# Sequencer1.net
KiCad netlist of a schematic drawn in EAGLE
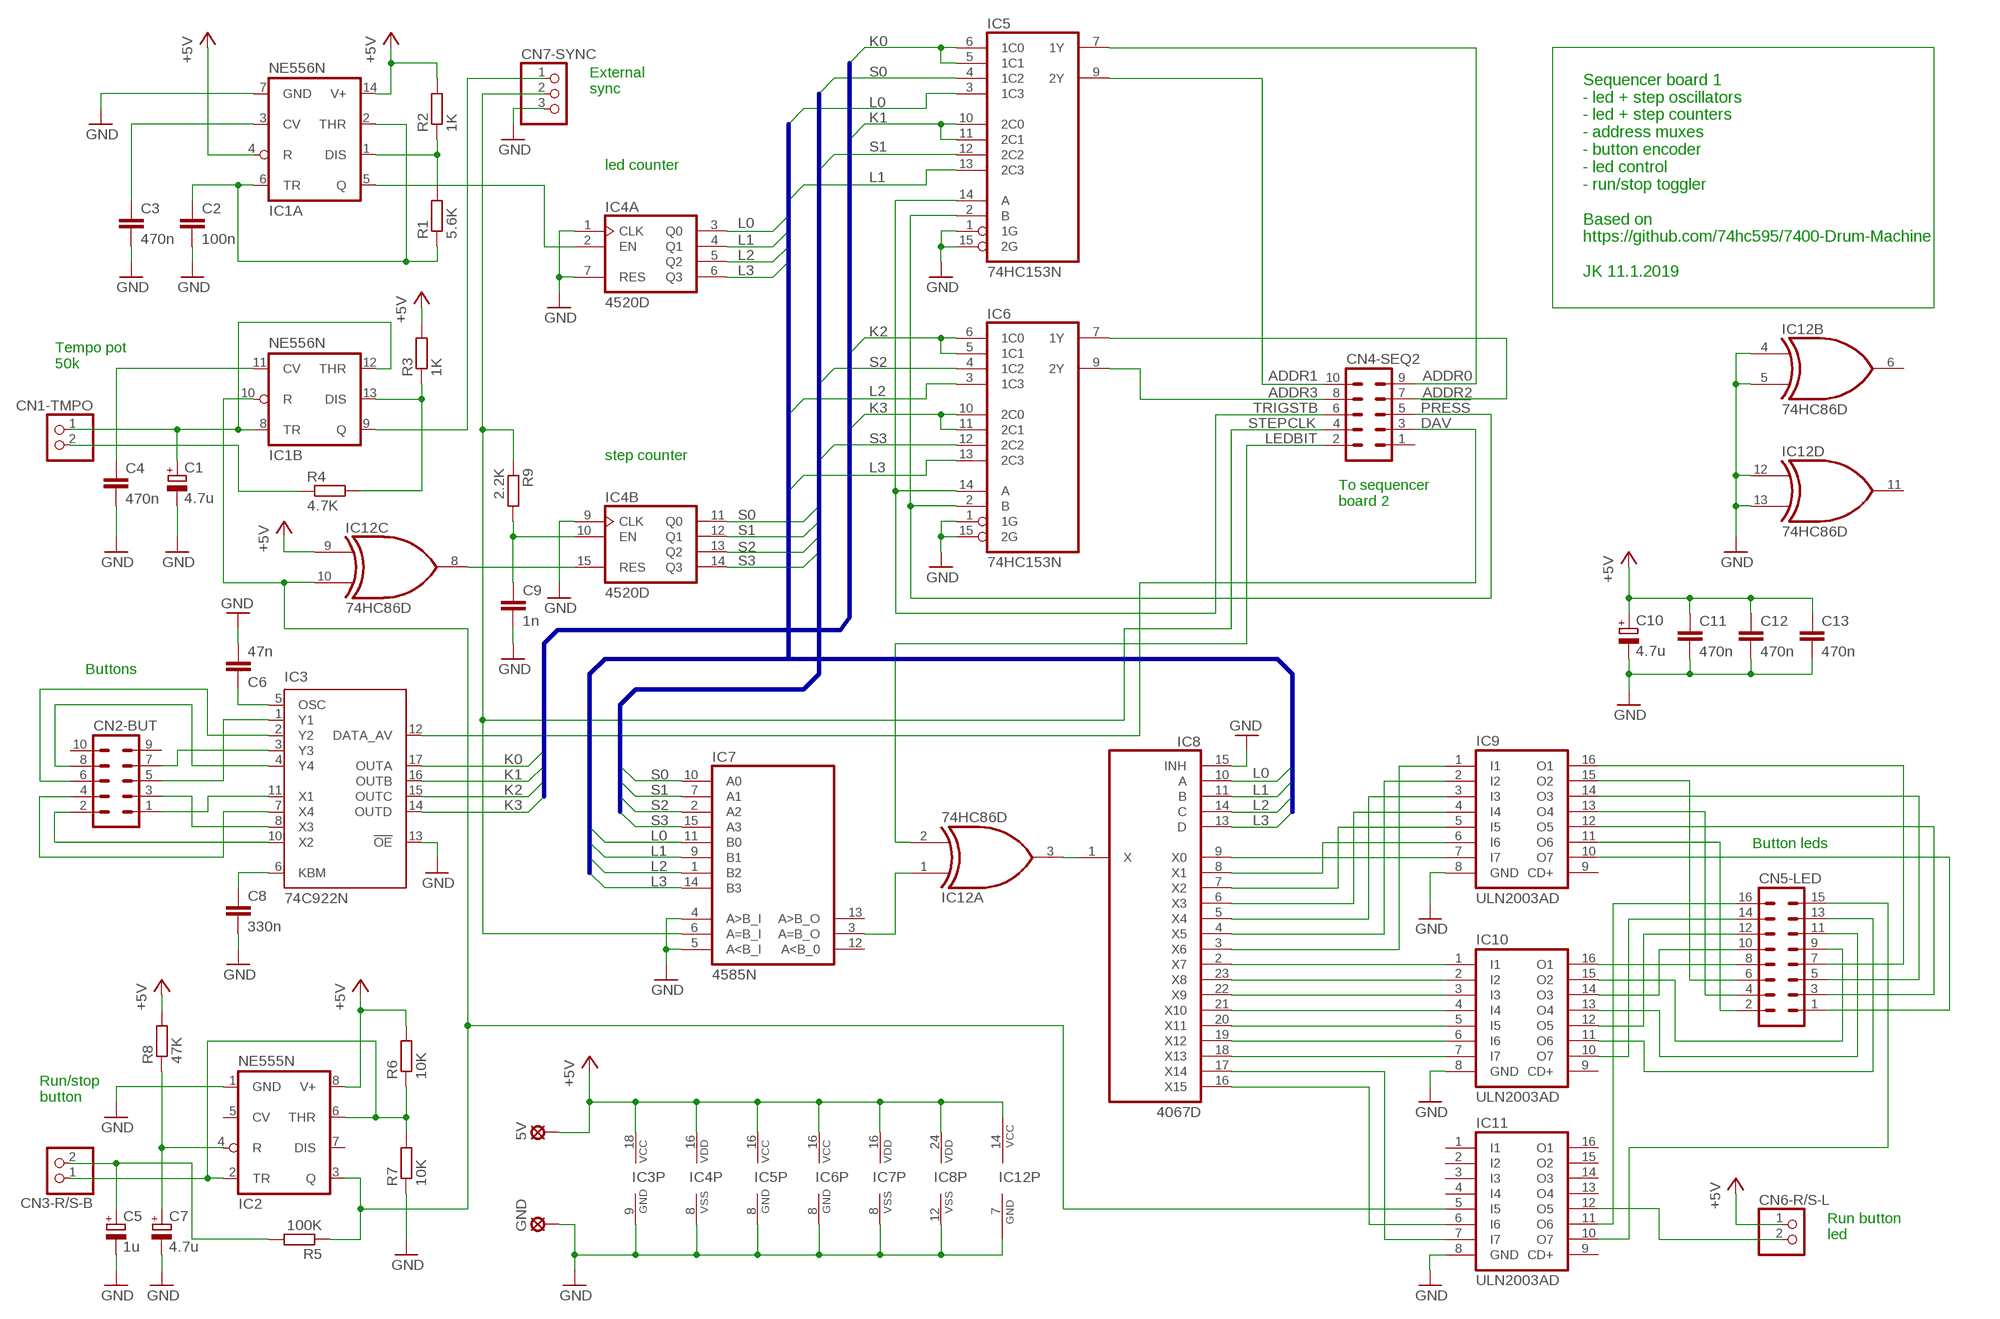
[diagram p0: schematic, sheet 1]

(export (version "E")
  (design (tool "Eeschema 10.0.6"))
  (components
    (comp (ref "5V")
      (value "LSP10")
      (footprint "eagle-import:LSP10")
      (libsource (lib "eagle-import") (part "LSP10"))
    )
    (comp (ref "C1")
      (value "4.7u")
      (footprint "eagle-import:SMC_A")
      (libsource (lib "eagle-import") (part "CPOL-EUSMCA"))
    )
    (comp (ref "C2")
      (value "100n")
      (footprint "eagle-import:C0805")
      (libsource (lib "eagle-import") (part "C-EUC0805"))
    )
    (comp (ref "C3")
      (value "470n")
      (footprint "eagle-import:C0603")
      (libsource (lib "eagle-import") (part "C-EUC0603"))
    )
    (comp (ref "C4")
      (value "470n")
      (footprint "eagle-import:C0603")
      (libsource (lib "eagle-import") (part "C-EUC0603"))
    )
    (comp (ref "C5")
      (value "1u")
      (footprint "eagle-import:SMC_A")
      (libsource (lib "eagle-import") (part "CPOL-EUSMCA"))
    )
    (comp (ref "C6")
      (value "47n")
      (footprint "eagle-import:C0805")
      (libsource (lib "eagle-import") (part "C-EUC0805"))
    )
    (comp (ref "C7")
      (value "4.7u")
      (footprint "eagle-import:SMC_A")
      (libsource (lib "eagle-import") (part "CPOL-EUSMCA"))
    )
    (comp (ref "C8")
      (value "330n")
      (footprint "eagle-import:C0805")
      (libsource (lib "eagle-import") (part "C-EUC0805"))
    )
    (comp (ref "C9")
      (value "1n")
      (footprint "eagle-import:C0805")
      (libsource (lib "eagle-import") (part "C-EUC0805"))
    )
    (comp (ref "C10")
      (value "4.7u")
      (footprint "eagle-import:SMC_A")
      (libsource (lib "eagle-import") (part "CPOL-EUSMCA"))
    )
    (comp (ref "C11")
      (value "470n")
      (footprint "eagle-import:C0603")
      (libsource (lib "eagle-import") (part "C-EUC0603"))
    )
    (comp (ref "C12")
      (value "470n")
      (footprint "eagle-import:C0603")
      (libsource (lib "eagle-import") (part "C-EUC0603"))
    )
    (comp (ref "C13")
      (value "470n")
      (footprint "eagle-import:C0603")
      (libsource (lib "eagle-import") (part "C-EUC0603"))
    )
    (comp (ref "CN1-TMPO")
      (value "PINHD-1X2")
      (footprint "eagle-import:1X02")
      (libsource (lib "eagle-import") (part "PINHD-1X2"))
    )
    (comp (ref "CN2-BUT")
      (value "MA05-2")
      (footprint "eagle-import:MA05-2")
      (libsource (lib "eagle-import") (part "MA05-2"))
    )
    (comp (ref "CN3-R/S-B")
      (value "PINHD-1X2")
      (footprint "eagle-import:1X02")
      (libsource (lib "eagle-import") (part "PINHD-1X2"))
    )
    (comp (ref "CN4-SEQ2")
      (value "MA05-2")
      (footprint "eagle-import:MA05-2")
      (libsource (lib "eagle-import") (part "MA05-2"))
    )
    (comp (ref "CN5-LED")
      (value "MA08-2")
      (footprint "eagle-import:MA08-2")
      (libsource (lib "eagle-import") (part "MA08-2"))
    )
    (comp (ref "CN6-R/S-L")
      (value "PINHD-1X2")
      (footprint "eagle-import:1X02")
      (libsource (lib "eagle-import") (part "PINHD-1X2"))
    )
    (comp (ref "CN7-SYNC")
      (value "PINHD-1X3")
      (footprint "eagle-import:1X03")
      (libsource (lib "eagle-import") (part "PINHD-1X3"))
    )
    (comp (ref "GND")
      (value "LSP10")
      (footprint "eagle-import:LSP10")
      (libsource (lib "eagle-import") (part "LSP10"))
    )
    (comp (ref "IC1")
      (value "NE556N")
      (footprint "eagle-import:DIL14")
      (libsource (lib "eagle-import") (part "556NNE"))
    )
    (comp (ref "IC2")
      (value "NE555N")
      (footprint "eagle-import:DIL08")
      (libsource (lib "eagle-import") (part "555NNE"))
    )
    (comp (ref "IC3")
      (value "74C922N")
      (footprint "eagle-import:DIL18")
      (libsource (lib "eagle-import") (part "74C922N"))
    )
    (comp (ref "IC4")
      (value "4520D")
      (footprint "eagle-import:SO16")
      (libsource (lib "eagle-import") (part "4520D"))
    )
    (comp (ref "IC5")
      (value "74HC153N")
      (footprint "eagle-import:DIL16")
      (libsource (lib "eagle-import") (part "74153NAC"))
    )
    (comp (ref "IC6")
      (value "74HC153N")
      (footprint "eagle-import:DIL16")
      (libsource (lib "eagle-import") (part "74153NAC"))
    )
    (comp (ref "IC7")
      (value "4585N")
      (footprint "eagle-import:DIL16")
      (libsource (lib "eagle-import") (part "4585N"))
    )
    (comp (ref "IC8")
      (value "4067D")
      (footprint "eagle-import:SO24W")
      (libsource (lib "eagle-import") (part "4067D"))
    )
    (comp (ref "IC9")
      (value "ULN2003AD")
      (footprint "eagle-import:SO16")
      (libsource (lib "eagle-import") (part "ULN2003AD"))
    )
    (comp (ref "IC10")
      (value "ULN2003AD")
      (footprint "eagle-import:SO16")
      (libsource (lib "eagle-import") (part "ULN2003AD"))
    )
    (comp (ref "IC11")
      (value "ULN2003AD")
      (footprint "eagle-import:SO16")
      (libsource (lib "eagle-import") (part "ULN2003AD"))
    )
    (comp (ref "IC12")
      (value "74HC86D")
      (footprint "eagle-import:SO14")
      (libsource (lib "eagle-import") (part "7486DLS"))
    )
    (comp (ref "R1")
      (value "5.6K")
      (footprint "eagle-import:R0805")
      (libsource (lib "eagle-import") (part "R-EU_R0805"))
    )
    (comp (ref "R2")
      (value "1K")
      (footprint "eagle-import:R0805")
      (libsource (lib "eagle-import") (part "R-EU_R0805"))
    )
    (comp (ref "R3")
      (value "1K")
      (footprint "eagle-import:R0805")
      (libsource (lib "eagle-import") (part "R-EU_R0805"))
    )
    (comp (ref "R4")
      (value "4.7K")
      (footprint "eagle-import:R0805")
      (libsource (lib "eagle-import") (part "R-EU_R0805"))
    )
    (comp (ref "R5")
      (value "100K")
      (footprint "eagle-import:R0805")
      (libsource (lib "eagle-import") (part "R-EU_R0805"))
    )
    (comp (ref "R6")
      (value "10K")
      (footprint "eagle-import:R0805")
      (libsource (lib "eagle-import") (part "R-EU_R0805"))
    )
    (comp (ref "R7")
      (value "10K")
      (footprint "eagle-import:R0805")
      (libsource (lib "eagle-import") (part "R-EU_R0805"))
    )
    (comp (ref "R8")
      (value "47K")
      (footprint "eagle-import:R0805")
      (libsource (lib "eagle-import") (part "R-EU_R0805"))
    )
    (comp (ref "R9")
      (value "2.2K")
      (footprint "eagle-import:R0805")
      (libsource (lib "eagle-import") (part "R-EU_R0805"))
    )
  )
  (nets
    (net (code "1") (name "+5V") (class "Default")
      (node (ref "5V") (pin "MP") (pinfunction "MP_MP") (pintype "passive"))
      (node (ref "C10") (pin "+") (pinfunction "+_+") (pintype "passive"))
      (node (ref "C11") (pin "1") (pinfunction "1_1") (pintype "passive"))
      (node (ref "C12") (pin "1") (pinfunction "1_1") (pintype "passive"))
      (node (ref "C13") (pin "1") (pinfunction "1_1") (pintype "passive"))
      (node (ref "CN6-R/S-L") (pin "1") (pinfunction "1_1") (pintype "passive"))
      (node (ref "IC1") (pin "14") (pinfunction "V+_14") (pintype "power_in"))
      (node (ref "IC1") (pin "4") (pinfunction "R_4") (pintype "input"))
      (node (ref "IC12") (pin "14") (pinfunction "VCC_14") (pintype "power_in"))
      (node (ref "IC12") (pin "9") (pinfunction "I0_9") (pintype "input"))
      (node (ref "IC2") (pin "8") (pinfunction "V+_8") (pintype "power_in"))
      (node (ref "IC3") (pin "18") (pinfunction "VCC_18") (pintype "power_in"))
      (node (ref "IC4") (pin "16") (pinfunction "VDD_16") (pintype "power_in"))
      (node (ref "IC5") (pin "16") (pinfunction "VCC_16") (pintype "power_in"))
      (node (ref "IC6") (pin "16") (pinfunction "VCC_16") (pintype "power_in"))
      (node (ref "IC7") (pin "16") (pinfunction "VDD_16") (pintype "power_in"))
      (node (ref "IC8") (pin "24") (pinfunction "VDD_24") (pintype "power_in"))
      (node (ref "R2") (pin "2") (pinfunction "2_2") (pintype "passive"))
      (node (ref "R3") (pin "2") (pinfunction "2_2") (pintype "passive"))
      (node (ref "R6") (pin "2") (pinfunction "2_2") (pintype "passive"))
      (node (ref "R8") (pin "2") (pinfunction "2_2") (pintype "passive"))
    )
    (net (code "2") (name "/ADDR0") (class "Default")
      (node (ref "CN4-SEQ2") (pin "9") (pinfunction "9_9") (pintype "passive"))
      (node (ref "IC5") (pin "7") (pinfunction "1Y_7") (pintype "output"))
    )
    (net (code "3") (name "/ADDR1") (class "Default")
      (node (ref "CN4-SEQ2") (pin "10") (pinfunction "10_10") (pintype "passive"))
      (node (ref "IC5") (pin "9") (pinfunction "2Y_9") (pintype "output"))
    )
    (net (code "4") (name "/ADDR2") (class "Default")
      (node (ref "CN4-SEQ2") (pin "7") (pinfunction "7_7") (pintype "passive"))
      (node (ref "IC6") (pin "7") (pinfunction "1Y_7") (pintype "output"))
    )
    (net (code "5") (name "/ADDR3") (class "Default")
      (node (ref "CN4-SEQ2") (pin "8") (pinfunction "8_8") (pintype "passive"))
      (node (ref "IC6") (pin "9") (pinfunction "2Y_9") (pintype "output"))
    )
    (net (code "6") (name "/DAV") (class "Default")
      (node (ref "CN4-SEQ2") (pin "3") (pinfunction "3_3") (pintype "passive"))
      (node (ref "IC3") (pin "12") (pinfunction "DATA_AV_12") (pintype "output"))
    )
    (net (code "7") (name "/K0") (class "Default")
      (node (ref "IC3") (pin "17") (pinfunction "OUTA_17") (pintype "output"))
      (node (ref "IC5") (pin "5") (pinfunction "1C1_5") (pintype "input"))
      (node (ref "IC5") (pin "6") (pinfunction "1C0_6") (pintype "input"))
    )
    (net (code "8") (name "/K1") (class "Default")
      (node (ref "IC3") (pin "16") (pinfunction "OUTB_16") (pintype "output"))
      (node (ref "IC5") (pin "10") (pinfunction "2C0_10") (pintype "input"))
      (node (ref "IC5") (pin "11") (pinfunction "2C1_11") (pintype "input"))
    )
    (net (code "9") (name "/K2") (class "Default")
      (node (ref "IC3") (pin "15") (pinfunction "OUTC_15") (pintype "output"))
      (node (ref "IC6") (pin "5") (pinfunction "1C1_5") (pintype "input"))
      (node (ref "IC6") (pin "6") (pinfunction "1C0_6") (pintype "input"))
    )
    (net (code "10") (name "/K3") (class "Default")
      (node (ref "IC3") (pin "14") (pinfunction "OUTD_14") (pintype "output"))
      (node (ref "IC6") (pin "10") (pinfunction "2C0_10") (pintype "input"))
      (node (ref "IC6") (pin "11") (pinfunction "2C1_11") (pintype "input"))
    )
    (net (code "11") (name "/L0") (class "Default")
      (node (ref "IC4") (pin "3") (pinfunction "Q0_3") (pintype "output"))
      (node (ref "IC5") (pin "3") (pinfunction "1C3_3") (pintype "input"))
      (node (ref "IC7") (pin "11") (pinfunction "B0_11") (pintype "input"))
      (node (ref "IC8") (pin "10") (pinfunction "A_10") (pintype "input"))
    )
    (net (code "12") (name "/L1") (class "Default")
      (node (ref "IC4") (pin "4") (pinfunction "Q1_4") (pintype "output"))
      (node (ref "IC5") (pin "13") (pinfunction "2C3_13") (pintype "input"))
      (node (ref "IC7") (pin "9") (pinfunction "B1_9") (pintype "input"))
      (node (ref "IC8") (pin "11") (pinfunction "B_11") (pintype "input"))
    )
    (net (code "13") (name "/L2") (class "Default")
      (node (ref "IC4") (pin "5") (pinfunction "Q2_5") (pintype "output"))
      (node (ref "IC6") (pin "3") (pinfunction "1C3_3") (pintype "input"))
      (node (ref "IC7") (pin "1") (pinfunction "B2_1") (pintype "input"))
      (node (ref "IC8") (pin "14") (pinfunction "C_14") (pintype "input"))
    )
    (net (code "14") (name "/L3") (class "Default")
      (node (ref "IC4") (pin "6") (pinfunction "Q3_6") (pintype "output"))
      (node (ref "IC6") (pin "13") (pinfunction "2C3_13") (pintype "input"))
      (node (ref "IC7") (pin "14") (pinfunction "B3_14") (pintype "input"))
      (node (ref "IC8") (pin "13") (pinfunction "D_13") (pintype "input"))
    )
    (net (code "15") (name "/LEDBIT") (class "Default")
      (node (ref "CN4-SEQ2") (pin "2") (pinfunction "2_2") (pintype "passive"))
      (node (ref "IC12") (pin "2") (pinfunction "I1_2") (pintype "input"))
    )
    (net (code "16") (name "/S0") (class "Default")
      (node (ref "IC4") (pin "11") (pinfunction "Q0_11") (pintype "output"))
      (node (ref "IC5") (pin "4") (pinfunction "1C2_4") (pintype "input"))
      (node (ref "IC7") (pin "10") (pinfunction "A0_10") (pintype "input"))
    )
    (net (code "17") (name "/S1") (class "Default")
      (node (ref "IC4") (pin "12") (pinfunction "Q1_12") (pintype "output"))
      (node (ref "IC5") (pin "12") (pinfunction "2C2_12") (pintype "input"))
      (node (ref "IC7") (pin "7") (pinfunction "A1_7") (pintype "input"))
    )
    (net (code "18") (name "/S2") (class "Default")
      (node (ref "IC4") (pin "13") (pinfunction "Q2_13") (pintype "output"))
      (node (ref "IC6") (pin "4") (pinfunction "1C2_4") (pintype "input"))
      (node (ref "IC7") (pin "2") (pinfunction "A2_2") (pintype "input"))
    )
    (net (code "19") (name "/S3") (class "Default")
      (node (ref "IC4") (pin "14") (pinfunction "Q3_14") (pintype "output"))
      (node (ref "IC6") (pin "12") (pinfunction "2C2_12") (pintype "input"))
      (node (ref "IC7") (pin "15") (pinfunction "A3_15") (pintype "input"))
    )
    (net (code "20") (name "/STEPCLK") (class "Default")
      (node (ref "CN4-SEQ2") (pin "4") (pinfunction "4_4") (pintype "passive"))
      (node (ref "CN7-SYNC") (pin "2") (pinfunction "2_2") (pintype "passive"))
      (node (ref "IC7") (pin "6") (pinfunction "A=B_I_6") (pintype "input"))
      (node (ref "R9") (pin "1") (pinfunction "1_1") (pintype "passive"))
    )
    (net (code "21") (name "/TRIGSTB") (class "Default")
      (node (ref "CN4-SEQ2") (pin "6") (pinfunction "6_6") (pintype "passive"))
      (node (ref "IC5") (pin "14") (pinfunction "A_14") (pintype "input"))
      (node (ref "IC6") (pin "14") (pinfunction "A_14") (pintype "input"))
    )
    (net (code "22") (name "/~{PRESS}") (class "Default")
      (node (ref "CN4-SEQ2") (pin "5") (pinfunction "5_5") (pintype "passive"))
      (node (ref "IC5") (pin "2") (pinfunction "B_2") (pintype "input"))
      (node (ref "IC6") (pin "2") (pinfunction "B_2") (pintype "input"))
    )
    (net (code "23") (name "GND") (class "Default")
      (node (ref "C1") (pin "-") (pinfunction "-_-") (pintype "passive"))
      (node (ref "C10") (pin "-") (pinfunction "-_-") (pintype "passive"))
      (node (ref "C11") (pin "2") (pinfunction "2_2") (pintype "passive"))
      (node (ref "C12") (pin "2") (pinfunction "2_2") (pintype "passive"))
      (node (ref "C13") (pin "2") (pinfunction "2_2") (pintype "passive"))
      (node (ref "C2") (pin "2") (pinfunction "2_2") (pintype "passive"))
      (node (ref "C3") (pin "2") (pinfunction "2_2") (pintype "passive"))
      (node (ref "C4") (pin "2") (pinfunction "2_2") (pintype "passive"))
      (node (ref "C5") (pin "-") (pinfunction "-_-") (pintype "passive"))
      (node (ref "C6") (pin "2") (pinfunction "2_2") (pintype "passive"))
      (node (ref "C7") (pin "-") (pinfunction "-_-") (pintype "passive"))
      (node (ref "C8") (pin "2") (pinfunction "2_2") (pintype "passive"))
      (node (ref "C9") (pin "2") (pinfunction "2_2") (pintype "passive"))
      (node (ref "CN7-SYNC") (pin "3") (pinfunction "3_3") (pintype "passive"))
      (node (ref "GND") (pin "MP") (pinfunction "MP_MP") (pintype "passive"))
      (node (ref "IC1") (pin "7") (pinfunction "GND_7") (pintype "power_in"))
      (node (ref "IC10") (pin "8") (pinfunction "GND_8") (pintype "power_in"))
      (node (ref "IC11") (pin "8") (pinfunction "GND_8") (pintype "power_in"))
      (node (ref "IC12") (pin "12") (pinfunction "I0_12") (pintype "input"))
      (node (ref "IC12") (pin "13") (pinfunction "I1_13") (pintype "input"))
      (node (ref "IC12") (pin "4") (pinfunction "I0_4") (pintype "input"))
      (node (ref "IC12") (pin "5") (pinfunction "I1_5") (pintype "input"))
      (node (ref "IC12") (pin "7") (pinfunction "GND_7") (pintype "power_in"))
      (node (ref "IC2") (pin "1") (pinfunction "GND_1") (pintype "power_in"))
      (node (ref "IC3") (pin "13") (pinfunction "~{OE}_13") (pintype "input"))
      (node (ref "IC3") (pin "9") (pinfunction "GND_9") (pintype "power_in"))
      (node (ref "IC4") (pin "1") (pinfunction "CLK_1") (pintype "input"))
      (node (ref "IC4") (pin "7") (pinfunction "RES_7") (pintype "input"))
      (node (ref "IC4") (pin "8") (pinfunction "VSS_8") (pintype "power_in"))
      (node (ref "IC4") (pin "9") (pinfunction "CLK_9") (pintype "input"))
      (node (ref "IC5") (pin "1") (pinfunction "1G_1") (pintype "input"))
      (node (ref "IC5") (pin "15") (pinfunction "2G_15") (pintype "input"))
      (node (ref "IC5") (pin "8") (pinfunction "GND_8") (pintype "power_in"))
      (node (ref "IC6") (pin "1") (pinfunction "1G_1") (pintype "input"))
      (node (ref "IC6") (pin "15") (pinfunction "2G_15") (pintype "input"))
      (node (ref "IC6") (pin "8") (pinfunction "GND_8") (pintype "power_in"))
      (node (ref "IC7") (pin "4") (pinfunction "A>B_I_4") (pintype "input"))
      (node (ref "IC7") (pin "5") (pinfunction "A<B_I_5") (pintype "input"))
      (node (ref "IC7") (pin "8") (pinfunction "VSS_8") (pintype "power_in"))
      (node (ref "IC8") (pin "12") (pinfunction "VSS_12") (pintype "power_in"))
      (node (ref "IC8") (pin "15") (pinfunction "INH_15") (pintype "input"))
      (node (ref "IC9") (pin "8") (pinfunction "GND_8") (pintype "power_in"))
      (node (ref "R7") (pin "1") (pinfunction "1_1") (pintype "passive"))
    )
    (net (code "24") (name "Net-(C5-Pad+)") (class "Default")
      (node (ref "C5") (pin "+") (pinfunction "+_+") (pintype "passive"))
      (node (ref "CN3-R/S-B") (pin "2") (pinfunction "2_2") (pintype "passive"))
      (node (ref "R5") (pin "2") (pinfunction "2_2") (pintype "passive"))
    )
    (net (code "25") (name "Net-(CN1-TMPO-Pad2)") (class "Default")
      (node (ref "CN1-TMPO") (pin "2") (pinfunction "2_2") (pintype "passive"))
      (node (ref "R4") (pin "1") (pinfunction "1_1") (pintype "passive"))
    )
    (net (code "26") (name "Net-(IC1A-CV)") (class "Default")
      (node (ref "C3") (pin "1") (pinfunction "1_1") (pintype "passive"))
      (node (ref "IC1") (pin "3") (pinfunction "CV_3") (pintype "input"))
    )
    (net (code "27") (name "Net-(IC1A-DIS)") (class "Default")
      (node (ref "IC1") (pin "1") (pinfunction "DIS_1") (pintype "input"))
      (node (ref "R1") (pin "2") (pinfunction "2_2") (pintype "passive"))
      (node (ref "R2") (pin "1") (pinfunction "1_1") (pintype "passive"))
    )
    (net (code "28") (name "Net-(IC1A-Q)") (class "Default")
      (node (ref "IC1") (pin "5") (pinfunction "Q_5") (pintype "output"))
      (node (ref "IC4") (pin "2") (pinfunction "EN_2") (pintype "input"))
    )
    (net (code "29") (name "Net-(IC1A-THR)") (class "Default")
      (node (ref "C2") (pin "1") (pinfunction "1_1") (pintype "passive"))
      (node (ref "IC1") (pin "2") (pinfunction "THR_2") (pintype "input"))
      (node (ref "IC1") (pin "6") (pinfunction "TR_6") (pintype "input"))
      (node (ref "R1") (pin "1") (pinfunction "1_1") (pintype "passive"))
    )
    (net (code "30") (name "Net-(IC1B-CV)") (class "Default")
      (node (ref "C4") (pin "1") (pinfunction "1_1") (pintype "passive"))
      (node (ref "IC1") (pin "11") (pinfunction "CV_11") (pintype "input"))
    )
    (net (code "31") (name "Net-(IC1B-DIS)") (class "Default")
      (node (ref "IC1") (pin "13") (pinfunction "DIS_13") (pintype "input"))
      (node (ref "R3") (pin "1") (pinfunction "1_1") (pintype "passive"))
      (node (ref "R4") (pin "2") (pinfunction "2_2") (pintype "passive"))
    )
    (net (code "32") (name "Net-(IC1B-Q)") (class "Default")
      (node (ref "CN7-SYNC") (pin "1") (pinfunction "1_1") (pintype "passive"))
      (node (ref "IC1") (pin "9") (pinfunction "Q_9") (pintype "output"))
    )
    (net (code "33") (name "Net-(IC1B-THR)") (class "Default")
      (node (ref "C1") (pin "+") (pinfunction "+_+") (pintype "passive"))
      (node (ref "CN1-TMPO") (pin "1") (pinfunction "1_1") (pintype "passive"))
      (node (ref "IC1") (pin "12") (pinfunction "THR_12") (pintype "input"))
      (node (ref "IC1") (pin "8") (pinfunction "TR_8") (pintype "input"))
    )
    (net (code "34") (name "Net-(IC2-R)") (class "Default")
      (node (ref "C7") (pin "+") (pinfunction "+_+") (pintype "passive"))
      (node (ref "IC2") (pin "4") (pinfunction "R_4") (pintype "input"))
      (node (ref "R8") (pin "1") (pinfunction "1_1") (pintype "passive"))
    )
    (net (code "35") (name "Net-(IC2-THR)") (class "Default")
      (node (ref "CN3-R/S-B") (pin "1") (pinfunction "1_1") (pintype "passive"))
      (node (ref "IC2") (pin "2") (pinfunction "TR_2") (pintype "input"))
      (node (ref "IC2") (pin "6") (pinfunction "THR_6") (pintype "input"))
      (node (ref "R6") (pin "1") (pinfunction "1_1") (pintype "passive"))
      (node (ref "R7") (pin "2") (pinfunction "2_2") (pintype "passive"))
    )
    (net (code "36") (name "Net-(IC3A-KBM)") (class "Default")
      (node (ref "C8") (pin "1") (pinfunction "1_1") (pintype "passive"))
      (node (ref "IC3") (pin "6") (pinfunction "KBM_6") (pintype "input"))
    )
    (net (code "37") (name "Net-(IC3A-OSC)") (class "Default")
      (node (ref "C6") (pin "1") (pinfunction "1_1") (pintype "passive"))
      (node (ref "IC3") (pin "5") (pinfunction "OSC_5") (pintype "input"))
    )
    (net (code "38") (name "Net-(IC3A-X1)") (class "Default")
      (node (ref "CN2-BUT") (pin "1") (pinfunction "1_1") (pintype "passive"))
      (node (ref "IC3") (pin "11") (pinfunction "X1_11") (pintype "input"))
    )
    (net (code "39") (name "Net-(IC3A-X2)") (class "Default")
      (node (ref "CN2-BUT") (pin "2") (pinfunction "2_2") (pintype "passive"))
      (node (ref "IC3") (pin "10") (pinfunction "X2_10") (pintype "input"))
    )
    (net (code "40") (name "Net-(IC3A-X3)") (class "Default")
      (node (ref "CN2-BUT") (pin "3") (pinfunction "3_3") (pintype "passive"))
      (node (ref "IC3") (pin "8") (pinfunction "X3_8") (pintype "input"))
    )
    (net (code "41") (name "Net-(IC3A-X4)") (class "Default")
      (node (ref "CN2-BUT") (pin "4") (pinfunction "4_4") (pintype "passive"))
      (node (ref "IC3") (pin "7") (pinfunction "X4_7") (pintype "input"))
    )
    (net (code "42") (name "Net-(IC3A-Y1)") (class "Default")
      (node (ref "CN2-BUT") (pin "5") (pinfunction "5_5") (pintype "passive"))
      (node (ref "IC3") (pin "1") (pinfunction "Y1_1") (pintype "input"))
    )
    (net (code "43") (name "Net-(IC3A-Y2)") (class "Default")
      (node (ref "CN2-BUT") (pin "6") (pinfunction "6_6") (pintype "passive"))
      (node (ref "IC3") (pin "2") (pinfunction "Y2_2") (pintype "input"))
    )
    (net (code "44") (name "Net-(IC3A-Y3)") (class "Default")
      (node (ref "CN2-BUT") (pin "7") (pinfunction "7_7") (pintype "passive"))
      (node (ref "IC3") (pin "3") (pinfunction "Y3_3") (pintype "input"))
    )
    (net (code "45") (name "Net-(IC3A-Y4)") (class "Default")
      (node (ref "CN2-BUT") (pin "8") (pinfunction "8_8") (pintype "passive"))
      (node (ref "IC3") (pin "4") (pinfunction "Y4_4") (pintype "input"))
    )
    (net (code "46") (name "Net-(IC4B-EN)") (class "Default")
      (node (ref "C9") (pin "1") (pinfunction "1_1") (pintype "passive"))
      (node (ref "IC4") (pin "10") (pinfunction "EN_10") (pintype "input"))
      (node (ref "R9") (pin "2") (pinfunction "2_2") (pintype "passive"))
    )
    (net (code "47") (name "Net-(IC8A-X0)") (class "Default")
      (node (ref "IC8") (pin "9") (pinfunction "X0_9") (pintype "input"))
      (node (ref "IC9") (pin "7") (pinfunction "I7_7") (pintype "input"))
    )
    (net (code "48") (name "Net-(IC8A-X1)") (class "Default")
      (node (ref "IC8") (pin "8") (pinfunction "X1_8") (pintype "input"))
      (node (ref "IC9") (pin "6") (pinfunction "I6_6") (pintype "input"))
    )
    (net (code "49") (name "Net-(IC8A-X2)") (class "Default")
      (node (ref "IC8") (pin "7") (pinfunction "X2_7") (pintype "input"))
      (node (ref "IC9") (pin "5") (pinfunction "I5_5") (pintype "input"))
    )
    (net (code "50") (name "Net-(IC8A-X3)") (class "Default")
      (node (ref "IC8") (pin "6") (pinfunction "X3_6") (pintype "input"))
      (node (ref "IC9") (pin "4") (pinfunction "I4_4") (pintype "input"))
    )
    (net (code "51") (name "Net-(IC8A-X4)") (class "Default")
      (node (ref "IC8") (pin "5") (pinfunction "X4_5") (pintype "input"))
      (node (ref "IC9") (pin "3") (pinfunction "I3_3") (pintype "input"))
    )
    (net (code "52") (name "Net-(IC8A-X5)") (class "Default")
      (node (ref "IC8") (pin "4") (pinfunction "X5_4") (pintype "input"))
      (node (ref "IC9") (pin "2") (pinfunction "I2_2") (pintype "input"))
    )
    (net (code "53") (name "Net-(IC8A-X6)") (class "Default")
      (node (ref "IC8") (pin "3") (pinfunction "X6_3") (pintype "input"))
      (node (ref "IC9") (pin "1") (pinfunction "I1_1") (pintype "input"))
    )
    (net (code "54") (name "Net-(IC9-O1)") (class "Default")
      (node (ref "CN5-LED") (pin "7") (pinfunction "7_7") (pintype "passive"))
      (node (ref "IC9") (pin "16") (pinfunction "O1_16") (pintype "open_collector"))
    )
    (net (code "55") (name "Net-(IC9-O2)") (class "Default")
      (node (ref "CN5-LED") (pin "6") (pinfunction "6_6") (pintype "passive"))
      (node (ref "IC9") (pin "15") (pinfunction "O2_15") (pintype "open_collector"))
    )
    (net (code "56") (name "Net-(IC9-O3)") (class "Default")
      (node (ref "CN5-LED") (pin "5") (pinfunction "5_5") (pintype "passive"))
      (node (ref "IC9") (pin "14") (pinfunction "O3_14") (pintype "open_collector"))
    )
    (net (code "57") (name "Net-(IC9-O4)") (class "Default")
      (node (ref "CN5-LED") (pin "4") (pinfunction "4_4") (pintype "passive"))
      (node (ref "IC9") (pin "13") (pinfunction "O4_13") (pintype "open_collector"))
    )
    (net (code "58") (name "Net-(IC9-O5)") (class "Default")
      (node (ref "CN5-LED") (pin "3") (pinfunction "3_3") (pintype "passive"))
      (node (ref "IC9") (pin "12") (pinfunction "O5_12") (pintype "open_collector"))
    )
    (net (code "59") (name "Net-(IC9-O6)") (class "Default")
      (node (ref "CN5-LED") (pin "2") (pinfunction "2_2") (pintype "passive"))
      (node (ref "IC9") (pin "11") (pinfunction "O6_11") (pintype "open_collector"))
    )
    (net (code "60") (name "Net-(IC9-O7)") (class "Default")
      (node (ref "CN5-LED") (pin "1") (pinfunction "1_1") (pintype "passive"))
      (node (ref "IC9") (pin "10") (pinfunction "O7_10") (pintype "open_collector"))
    )
    (net (code "61") (name "Net-(IC10-I1)") (class "Default")
      (node (ref "IC10") (pin "1") (pinfunction "I1_1") (pintype "input"))
      (node (ref "IC8") (pin "2") (pinfunction "X7_2") (pintype "input"))
    )
    (net (code "62") (name "Net-(IC10-I2)") (class "Default")
      (node (ref "IC10") (pin "2") (pinfunction "I2_2") (pintype "input"))
      (node (ref "IC8") (pin "23") (pinfunction "X8_23") (pintype "input"))
    )
    (net (code "63") (name "Net-(IC10-I3)") (class "Default")
      (node (ref "IC10") (pin "3") (pinfunction "I3_3") (pintype "input"))
      (node (ref "IC8") (pin "22") (pinfunction "X9_22") (pintype "input"))
    )
    (net (code "64") (name "Net-(IC10-I4)") (class "Default")
      (node (ref "IC10") (pin "4") (pinfunction "I4_4") (pintype "input"))
      (node (ref "IC8") (pin "21") (pinfunction "X10_21") (pintype "input"))
    )
    (net (code "65") (name "Net-(IC10-I5)") (class "Default")
      (node (ref "IC10") (pin "5") (pinfunction "I5_5") (pintype "input"))
      (node (ref "IC8") (pin "20") (pinfunction "X11_20") (pintype "input"))
    )
    (net (code "66") (name "Net-(IC10-I6)") (class "Default")
      (node (ref "IC10") (pin "6") (pinfunction "I6_6") (pintype "input"))
      (node (ref "IC8") (pin "19") (pinfunction "X12_19") (pintype "input"))
    )
    (net (code "67") (name "Net-(IC10-I7)") (class "Default")
      (node (ref "IC10") (pin "7") (pinfunction "I7_7") (pintype "input"))
      (node (ref "IC8") (pin "18") (pinfunction "X13_18") (pintype "input"))
    )
    (net (code "68") (name "Net-(IC10-O1)") (class "Default")
      (node (ref "CN5-LED") (pin "8") (pinfunction "8_8") (pintype "passive"))
      (node (ref "IC10") (pin "16") (pinfunction "O1_16") (pintype "open_collector"))
    )
    (net (code "69") (name "Net-(IC10-O2)") (class "Default")
      (node (ref "CN5-LED") (pin "9") (pinfunction "9_9") (pintype "passive"))
      (node (ref "IC10") (pin "15") (pinfunction "O2_15") (pintype "open_collector"))
    )
    (net (code "70") (name "Net-(IC10-O3)") (class "Default")
      (node (ref "CN5-LED") (pin "10") (pinfunction "10_10") (pintype "passive"))
      (node (ref "IC10") (pin "14") (pinfunction "O3_14") (pintype "open_collector"))
    )
    (net (code "71") (name "Net-(IC10-O4)") (class "Default")
      (node (ref "CN5-LED") (pin "11") (pinfunction "11_11") (pintype "passive"))
      (node (ref "IC10") (pin "13") (pinfunction "O4_13") (pintype "open_collector"))
    )
    (net (code "72") (name "Net-(IC10-O5)") (class "Default")
      (node (ref "CN5-LED") (pin "12") (pinfunction "12_12") (pintype "passive"))
      (node (ref "IC10") (pin "12") (pinfunction "O5_12") (pintype "open_collector"))
    )
    (net (code "73") (name "Net-(IC10-O6)") (class "Default")
      (node (ref "CN5-LED") (pin "13") (pinfunction "13_13") (pintype "passive"))
      (node (ref "IC10") (pin "11") (pinfunction "O6_11") (pintype "open_collector"))
    )
    (net (code "74") (name "Net-(IC10-O7)") (class "Default")
      (node (ref "CN5-LED") (pin "14") (pinfunction "14_14") (pintype "passive"))
      (node (ref "IC10") (pin "10") (pinfunction "O7_10") (pintype "open_collector"))
    )
    (net (code "75") (name "Net-(IC11-I5)") (class "Default")
      (node (ref "IC1") (pin "10") (pinfunction "R_10") (pintype "input"))
      (node (ref "IC11") (pin "5") (pinfunction "I5_5") (pintype "input"))
      (node (ref "IC12") (pin "10") (pinfunction "I1_10") (pintype "input"))
      (node (ref "IC2") (pin "3") (pinfunction "Q_3") (pintype "output"))
      (node (ref "R5") (pin "1") (pinfunction "1_1") (pintype "passive"))
    )
    (net (code "76") (name "Net-(IC11-I6)") (class "Default")
      (node (ref "IC11") (pin "6") (pinfunction "I6_6") (pintype "input"))
      (node (ref "IC8") (pin "16") (pinfunction "X15_16") (pintype "input"))
    )
    (net (code "77") (name "Net-(IC11-I7)") (class "Default")
      (node (ref "IC11") (pin "7") (pinfunction "I7_7") (pintype "input"))
      (node (ref "IC8") (pin "17") (pinfunction "X14_17") (pintype "input"))
    )
    (net (code "78") (name "Net-(IC11-O5)") (class "Default")
      (node (ref "CN6-R/S-L") (pin "2") (pinfunction "2_2") (pintype "passive"))
      (node (ref "IC11") (pin "12") (pinfunction "O5_12") (pintype "open_collector"))
    )
    (net (code "79") (name "Net-(IC11-O6)") (class "Default")
      (node (ref "CN5-LED") (pin "16") (pinfunction "16_16") (pintype "passive"))
      (node (ref "IC11") (pin "11") (pinfunction "O6_11") (pintype "open_collector"))
    )
    (net (code "80") (name "Net-(IC11-O7)") (class "Default")
      (node (ref "CN5-LED") (pin "15") (pinfunction "15_15") (pintype "passive"))
      (node (ref "IC11") (pin "10") (pinfunction "O7_10") (pintype "open_collector"))
    )
    (net (code "81") (name "Net-(IC12A-I0)") (class "Default")
      (node (ref "IC12") (pin "1") (pinfunction "I0_1") (pintype "input"))
      (node (ref "IC7") (pin "3") (pinfunction "A=B_O_3") (pintype "output"))
    )
    (net (code "82") (name "Net-(IC12A-O)") (class "Default")
      (node (ref "IC12") (pin "3") (pinfunction "O_3") (pintype "output"))
      (node (ref "IC8") (pin "1") (pinfunction "X_1") (pintype "output"))
    )
    (net (code "83") (name "Net-(IC12C-O)") (class "Default")
      (node (ref "IC12") (pin "8") (pinfunction "O_8") (pintype "output"))
      (node (ref "IC4") (pin "15") (pinfunction "RES_15") (pintype "input"))
    )
    (net (code "84") (name "unconnected-(CN2-BUT-Pad9)") (class "Default")
      (node (ref "CN2-BUT") (pin "9") (pinfunction "9_9") (pintype "passive"))
    )
    (net (code "85") (name "unconnected-(CN2-BUT-Pad10)") (class "Default")
      (node (ref "CN2-BUT") (pin "10") (pinfunction "10_10") (pintype "passive"))
    )
    (net (code "86") (name "unconnected-(CN4-SEQ2-Pad1)") (class "Default")
      (node (ref "CN4-SEQ2") (pin "1") (pinfunction "1_1") (pintype "passive"))
    )
    (net (code "87") (name "unconnected-(IC2-CV-Pad5)") (class "Default")
      (node (ref "IC2") (pin "5") (pinfunction "CV_5") (pintype "input"))
    )
    (net (code "88") (name "unconnected-(IC2-DIS-Pad7)") (class "Default")
      (node (ref "IC2") (pin "7") (pinfunction "DIS_7") (pintype "input"))
    )
    (net (code "89") (name "unconnected-(IC7A-A<B_0-Pad12)") (class "Default")
      (node (ref "IC7") (pin "12") (pinfunction "A<B_0_12") (pintype "output"))
    )
    (net (code "90") (name "unconnected-(IC7A-A>B_O-Pad13)") (class "Default")
      (node (ref "IC7") (pin "13") (pinfunction "A>B_O_13") (pintype "output"))
    )
    (net (code "91") (name "unconnected-(IC9-CD+-Pad9)") (class "Default")
      (node (ref "IC9") (pin "9") (pinfunction "CD+_9") (pintype "passive"))
    )
    (net (code "92") (name "unconnected-(IC10-CD+-Pad9)") (class "Default")
      (node (ref "IC10") (pin "9") (pinfunction "CD+_9") (pintype "passive"))
    )
    (net (code "93") (name "unconnected-(IC11-CD+-Pad9)") (class "Default")
      (node (ref "IC11") (pin "9") (pinfunction "CD+_9") (pintype "passive"))
    )
    (net (code "94") (name "unconnected-(IC11-I1-Pad1)") (class "Default")
      (node (ref "IC11") (pin "1") (pinfunction "I1_1") (pintype "input"))
    )
    (net (code "95") (name "unconnected-(IC11-I2-Pad2)") (class "Default")
      (node (ref "IC11") (pin "2") (pinfunction "I2_2") (pintype "input"))
    )
    (net (code "96") (name "unconnected-(IC11-I3-Pad3)") (class "Default")
      (node (ref "IC11") (pin "3") (pinfunction "I3_3") (pintype "input"))
    )
    (net (code "97") (name "unconnected-(IC11-I4-Pad4)") (class "Default")
      (node (ref "IC11") (pin "4") (pinfunction "I4_4") (pintype "input"))
    )
    (net (code "98") (name "unconnected-(IC11-O1-Pad16)") (class "Default")
      (node (ref "IC11") (pin "16") (pinfunction "O1_16") (pintype "open_collector"))
    )
    (net (code "99") (name "unconnected-(IC11-O2-Pad15)") (class "Default")
      (node (ref "IC11") (pin "15") (pinfunction "O2_15") (pintype "open_collector"))
    )
    (net (code "100") (name "unconnected-(IC11-O3-Pad14)") (class "Default")
      (node (ref "IC11") (pin "14") (pinfunction "O3_14") (pintype "open_collector"))
    )
    (net (code "101") (name "unconnected-(IC11-O4-Pad13)") (class "Default")
      (node (ref "IC11") (pin "13") (pinfunction "O4_13") (pintype "open_collector"))
    )
    (net (code "102") (name "unconnected-(IC12B-O-Pad6)") (class "Default")
      (node (ref "IC12") (pin "6") (pinfunction "O_6") (pintype "output"))
    )
    (net (code "103") (name "unconnected-(IC12D-O-Pad11)") (class "Default")
      (node (ref "IC12") (pin "11") (pinfunction "O_11") (pintype "output"))
    )
  )
)
